# stm8_sensor.net
KiCad netlist of a schematic drawn in Altium Designer
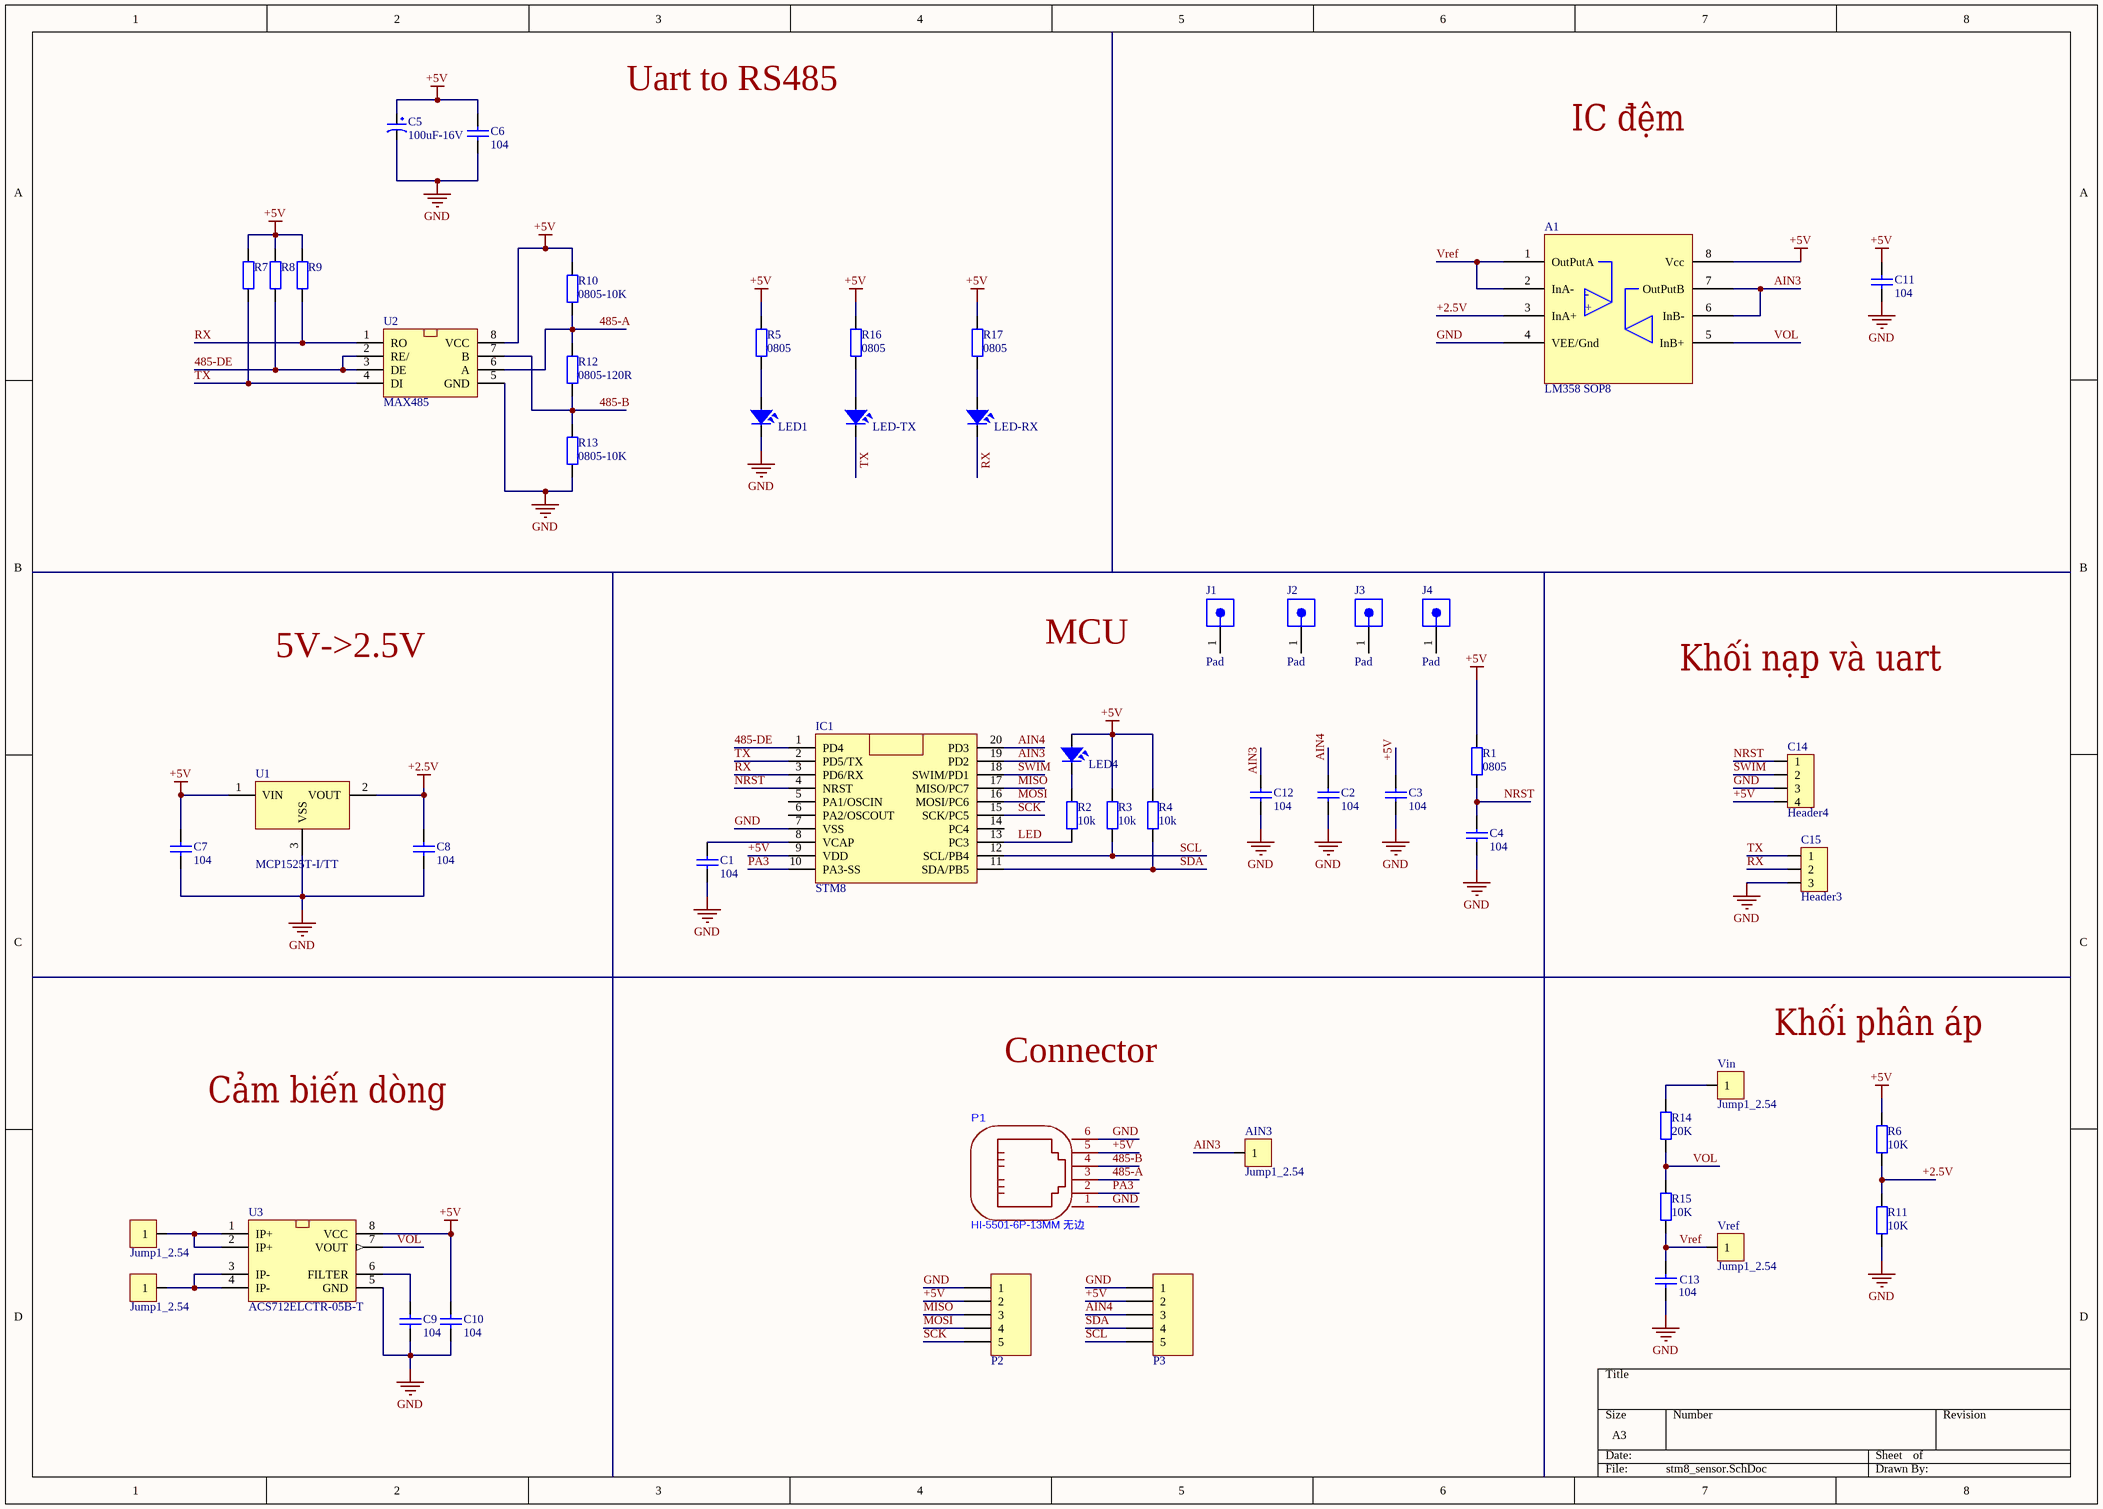
[diagram p0: stm8_sensor.SchDoc]

(export (version "E")
  (design (tool "Eeschema 10.0.6"))
  (components
    (comp (ref "A1")
      (value "LM358 SOP8")
      (footprint "LM358_SOIC")
      (description "Dán")
      (libsource (lib "THU VIEN SCH") (part "LM358"))
    )
    (comp (ref "AIN3")
      (value "Jump1_2.54")
      (footprint "jump1_2.54")
      (libsource (lib "thuviencuazit") (part "jump_1"))
    )
    (comp (ref "C1")
      (value "104")
      (footprint "0805")
      (description "Capacitor (Semiconductor SIM Model)")
      (fields (field (name "PUBLISHER") "Altium Limited"))
      (libsource (lib "Altium_Devzone") (part "Cap 104_SMD"))
    )
    (comp (ref "C2")
      (value "104")
      (footprint "0805")
      (description "Capacitor (Semiconductor SIM Model)")
      (fields (field (name "PUBLISHER") "Altium Limited"))
      (libsource (lib "Altium_Devzone") (part "Cap 104_SMD"))
    )
    (comp (ref "C3")
      (value "104")
      (footprint "0805")
      (description "Capacitor (Semiconductor SIM Model)")
      (fields (field (name "PUBLISHER") "Altium Limited"))
      (libsource (lib "Altium_Devzone") (part "Cap 104_SMD"))
    )
    (comp (ref "C4")
      (value "104")
      (footprint "0805")
      (description "Capacitor (Semiconductor SIM Model)")
      (fields (field (name "PUBLISHER") "Altium Limited"))
      (libsource (lib "Altium_Devzone") (part "Cap 104_SMD"))
    )
    (comp (ref "C5")
      (value "100uF-16V")
      (footprint "tu tantalum smd3216")
      (description "Dán")
      (libsource (lib "THU VIEN SCH") (part "Tu tantalum 1uF 35V SMD3216"))
    )
    (comp (ref "C6")
      (value "104")
      (footprint "tu 0805")
      (description "Dán")
      (libsource (lib "THU VIEN SCH") (part "Tu 0805 104 50V 10%"))
    )
    (comp (ref "C7")
      (value "104")
      (footprint "Tu 0805")
      (description "Dán")
      (libsource (lib "THU VIEN SCH") (part "Tu 104"))
    )
    (comp (ref "C8")
      (value "104")
      (footprint "Tu 0805")
      (description "Dán")
      (libsource (lib "THU VIEN SCH") (part "Tu 104"))
    )
    (comp (ref "C9")
      (value "104")
      (footprint "Tu 0805")
      (description "Dán")
      (libsource (lib "THU VIEN SCH") (part "Tu 104"))
    )
    (comp (ref "C10")
      (value "104")
      (footprint "Tu 0805")
      (description "Dán")
      (libsource (lib "THU VIEN SCH") (part "Tu 104"))
    )
    (comp (ref "C11")
      (value "104")
      (footprint "Tu 0805")
      (description "Dán")
      (libsource (lib "THU VIEN SCH") (part "Tu 104"))
    )
    (comp (ref "C12")
      (value "104")
      (footprint "0805")
      (description "Capacitor (Semiconductor SIM Model)")
      (fields (field (name "PUBLISHER") "Altium Limited"))
      (libsource (lib "Altium_Devzone") (part "Cap 104_SMD"))
    )
    (comp (ref "C13")
      (value "104")
      (footprint "Tu 0805")
      (description "Dán")
      (libsource (lib "THU VIEN SCH") (part "Tu 104"))
    )
    (comp (ref "C14")
      (value "Header4")
      (footprint "Header4")
      (description "Header IDC, 4 x 1 Pin Vertical 2.54mm Pitch (Non-Boxed, Male)")
      (fields
        (field (name "MANUFACTURER") "Würth Elektronik eiSos GmbH")
        (field (name "PARTNO") "613002143121")
        (field (name "CREATED BY") "Karrer Zheng")
      )
      (libsource (lib "Altium_Devzone") (part "Header4"))
    )
    (comp (ref "C15")
      (value "Header3")
      (footprint "Header3")
      (description "Header IDC, 3 x 1 Pin Vertical 2.54mm Pitch (Non-Boxed, Male)")
      (fields
        (field (name "MANUFACTURER") "Würth Elektronik eiSos GmbH")
        (field (name "PARTNO") "613002143121")
        (field (name "CREATED BY") "Karrer Zheng")
      )
      (libsource (lib "Altium_Devzone") (part "Header3"))
    )
    (comp (ref "IC1")
      (value "STM8")
      (footprint "TSSOP 20PIN")
      (description "STM32 ARM MCU")
      (libsource (lib "Altium_Devzone") (part "STM8S103F3_20P"))
    )
    (comp (ref "IP+") (value "Jump1_2.54") (footprint "jump1_2.54") (libsource (lib "") (part "jump_1_1")))
    (comp (ref "IP-") (value "Jump1_2.54") (footprint "jump1_2.54") (libsource (lib "") (part "jump_1_1")))
    (comp (ref "J1")
      (value "Pad")
      (footprint "MinhTien_PCBLib:Pad_4.5x4.5_hole_3.2mm_no_legend")
      (fields (field (name "PUBLISHER") "Altium Limited"))
      (libsource (lib "MinhTien_SCHLib") (part "Pad"))
    )
    (comp (ref "J2")
      (value "Pad")
      (footprint "MinhTien_PCBLib:Pad_4.5x4.5_hole_3.2mm_no_legend")
      (fields (field (name "PUBLISHER") "Altium Limited"))
      (libsource (lib "MinhTien_SCHLib") (part "Pad"))
    )
    (comp (ref "J3")
      (value "Pad")
      (footprint "MinhTien_PCBLib:Pad_4.5x4.5_hole_3.2mm_no_legend")
      (fields (field (name "PUBLISHER") "Altium Limited"))
      (libsource (lib "MinhTien_SCHLib") (part "Pad"))
    )
    (comp (ref "J4")
      (value "Pad")
      (footprint "MinhTien_PCBLib:Pad_4.5x4.5_hole_3.2mm_no_legend")
      (fields (field (name "PUBLISHER") "Altium Limited"))
      (libsource (lib "MinhTien_SCHLib") (part "Pad"))
    )
    (comp (ref "LED-RX")
      (value "LED")
      (footprint "LED-5-Green")
      (description "LED Single colour Green and Red")
      (libsource (lib "Altium_Devzone") (part "LED"))
    )
    (comp (ref "LED-TX")
      (value "LED")
      (footprint "LED-5-BLUE")
      (description "LED Single colour Green and Red")
      (libsource (lib "Altium_Devzone") (part "LED"))
    )
    (comp (ref "LED1")
      (value "LED")
      (footprint "LED-5-Yellow")
      (description "LED Single colour Green and Red")
      (libsource (lib "Altium_Devzone") (part "LED"))
    )
    (comp (ref "LED4")
      (value "LED")
      (footprint "LED-5-RED")
      (description "LED Single colour Green and Red")
      (libsource (lib "Altium_Devzone") (part "LED"))
    )
    (comp (ref "P1")
      (value "HI-5501-6P-13MM 无边")
      (footprint "RJ11-TH_PCB-6P6C-90")
      (libsource (lib "thuviencuazit") (part "HI-5501-6P-13MM 无边"))
    )
    (comp (ref "P2")
      (value "Connector")
      (footprint "MinhTien_PCBLib:JST-XH_B5B-XH-A")
      (libsource (lib "MinhTien_SCHLib") (part "Connector_5pin"))
    )
    (comp (ref "P3")
      (value "Connector")
      (footprint "MinhTien_PCBLib:JST-XH_B5B-XH-A")
      (libsource (lib "MinhTien_SCHLib") (part "Connector_5pin"))
    )
    (comp (ref "R1")
      (value "0805")
      (footprint "DIEN TRO 0805")
      (description "Resistor SMD 0805")
      (fields (field (name "Comment") "R0805") (field (name "PUBLISHER") "Altium Limited"))
      (libsource (lib "Altium_Devzone") (part "R0805"))
    )
    (comp (ref "R2")
      (value "10k")
      (footprint "DIEN TRO 0805")
      (description "Resistor SMD 0805")
      (fields (field (name "Comment") "R0805") (field (name "PUBLISHER") "Altium Limited"))
      (libsource (lib "Altium_Devzone") (part "R0805"))
    )
    (comp (ref "R3")
      (value "10k")
      (footprint "DIEN TRO 0805")
      (description "Resistor SMD 0805")
      (fields (field (name "Comment") "R0805") (field (name "PUBLISHER") "Altium Limited"))
      (libsource (lib "Altium_Devzone") (part "R0805"))
    )
    (comp (ref "R4")
      (value "10k")
      (footprint "DIEN TRO 0805")
      (description "Resistor SMD 0805")
      (fields (field (name "Comment") "R0805") (field (name "PUBLISHER") "Altium Limited"))
      (libsource (lib "Altium_Devzone") (part "R0805"))
    )
    (comp (ref "R5")
      (value "0805")
      (footprint "DIEN TRO 0805")
      (description "Resistor SMD 0805")
      (fields (field (name "Comment") "R0805") (field (name "PUBLISHER") "Altium Limited"))
      (libsource (lib "Altium_Devzone") (part "R0805"))
    )
    (comp (ref "R6")
      (value "10K")
      (footprint "DIEN TRO 0805")
      (description "Resistor SMD 0805")
      (fields (field (name "Comment") "R0805") (field (name "PUBLISHER") "Altium Limited"))
      (libsource (lib "Altium_Devzone") (part "R0805"))
    )
    (comp (ref "R7")
      (value "R0805")
      (footprint "DIEN TRO 0805")
      (description "Resistor SMD 0805")
      (fields (field (name "PUBLISHER") "Altium Limited"))
      (libsource (lib "Altium_Devzone") (part "R0805"))
    )
    (comp (ref "R8")
      (value "R0805")
      (footprint "DIEN TRO 0805")
      (description "Resistor SMD 0805")
      (fields (field (name "PUBLISHER") "Altium Limited"))
      (libsource (lib "Altium_Devzone") (part "R0805"))
    )
    (comp (ref "R9")
      (value "R0805")
      (footprint "DIEN TRO 0805")
      (description "Resistor SMD 0805")
      (fields (field (name "PUBLISHER") "Altium Limited"))
      (libsource (lib "Altium_Devzone") (part "R0805"))
    )
    (comp (ref "R10")
      (value "0805-10K")
      (footprint "DIEN TRO 0805")
      (description "Resistor SMD 0805")
      (fields (field (name "Comment") "R0805") (field (name "PUBLISHER") "Altium Limited"))
      (libsource (lib "Altium_Devzone") (part "R0805"))
    )
    (comp (ref "R11")
      (value "10K")
      (footprint "DIEN TRO 0805")
      (description "Resistor SMD 0805")
      (fields (field (name "Comment") "R0805") (field (name "PUBLISHER") "Altium Limited"))
      (libsource (lib "Altium_Devzone") (part "R0805"))
    )
    (comp (ref "R12")
      (value "0805-120R")
      (footprint "DIEN TRO 0805")
      (description "Resistor SMD 0805")
      (fields (field (name "Comment") "R0805") (field (name "PUBLISHER") "Altium Limited"))
      (libsource (lib "Altium_Devzone") (part "R0805"))
    )
    (comp (ref "R13")
      (value "0805-10K")
      (footprint "DIEN TRO 0805")
      (description "Resistor SMD 0805")
      (fields (field (name "Comment") "R0805") (field (name "PUBLISHER") "Altium Limited"))
      (libsource (lib "Altium_Devzone") (part "R0805"))
    )
    (comp (ref "R14")
      (value "20K")
      (footprint "DIEN TRO 0805")
      (description "Resistor SMD 0805")
      (fields (field (name "Comment") "R0805") (field (name "PUBLISHER") "Altium Limited"))
      (libsource (lib "Altium_Devzone") (part "R0805"))
    )
    (comp (ref "R15")
      (value "10K")
      (footprint "DIEN TRO 0805")
      (description "Resistor SMD 0805")
      (fields (field (name "Comment") "R0805") (field (name "PUBLISHER") "Altium Limited"))
      (libsource (lib "Altium_Devzone") (part "R0805"))
    )
    (comp (ref "R16")
      (value "0805")
      (footprint "DIEN TRO 0805")
      (description "Resistor SMD 0805")
      (fields (field (name "Comment") "R0805") (field (name "PUBLISHER") "Altium Limited"))
      (libsource (lib "Altium_Devzone") (part "R0805"))
    )
    (comp (ref "R17")
      (value "0805")
      (footprint "DIEN TRO 0805")
      (description "Resistor SMD 0805")
      (fields (field (name "Comment") "R0805") (field (name "PUBLISHER") "Altium Limited"))
      (libsource (lib "Altium_Devzone") (part "R0805"))
    )
    (comp (ref "U1")
      (value "MCP1525T-I/TT")
      (footprint "MinhTien_PCBLib:SOT23")
      (description "2.5V And 4.096V Voltage References")
      (libsource (lib "MinhTien_SCHLib") (part "MCP1525T"))
    )
    (comp (ref "U2")
      (value "MAX485")
      (footprint "MinhTien_PcbLib:SOP8_L")
      (libsource (lib "MinhTien_SCHLib") (part "MAX485"))
    )
    (comp (ref "U3")
      (value "ACS712ELCTR-05B-T")
      (footprint "MinhTien_PcbLib:SOP8_L")
      (description "SENSOR CURRENT HALL 5A AC/DC")
      (libsource (lib "MinhTien_SCHLib") (part "ACS712ELCTR-05B-T"))
    )
    (comp (ref "Vin")
      (value "Jump1_2.54")
      (footprint "jump1_2.54")
      (libsource (lib "thuviencuazit") (part "jump_1"))
    )
    (comp (ref "Vref")
      (value "Jump1_2.54")
      (footprint "jump1_2.54")
      (libsource (lib "thuviencuazit") (part "jump_1"))
    )
  )
  (nets
    (net (code "1") (name "+2.5V") (class "Default")
      (node (ref "A1") (pin "3") (pinfunction "InA+_3") (pintype "passive"))
      (node (ref "C8") (pin "2") (pinfunction "2_2") (pintype "passive"))
      (node (ref "R11") (pin "2") (pinfunction "2_2") (pintype "passive"))
      (node (ref "R6") (pin "1") (pinfunction "1_1") (pintype "passive"))
      (node (ref "U1") (pin "2") (pinfunction "VOUT_2") (pintype "passive"))
    )
    (net (code "2") (name "+5V") (class "Default")
      (node (ref "A1") (pin "8") (pinfunction "Vcc_8") (pintype "passive"))
      (node (ref "C10") (pin "2") (pinfunction "2_2") (pintype "passive"))
      (node (ref "C11") (pin "2") (pinfunction "2_2") (pintype "passive"))
      (node (ref "C14") (pin "4") (pinfunction "4_4") (pintype "passive"))
      (node (ref "C3") (pin "2") (pintype "passive"))
      (node (ref "C5") (pin "1") (pinfunction "1_1") (pintype "passive"))
      (node (ref "C6") (pin "1") (pinfunction "1_1") (pintype "passive"))
      (node (ref "C7") (pin "2") (pinfunction "2_2") (pintype "passive"))
      (node (ref "IC1") (pin "9") (pinfunction "VDD_9") (pintype "passive"))
      (node (ref "LED4") (pin "1") (pinfunction "1_1") (pintype "passive"))
      (node (ref "P1") (pin "5") (pinfunction "5_5") (pintype "passive"))
      (node (ref "P2") (pin "2") (pinfunction "2_2") (pintype "passive"))
      (node (ref "P3") (pin "2") (pinfunction "2_2") (pintype "passive"))
      (node (ref "R1") (pin "2") (pinfunction "2_2") (pintype "passive"))
      (node (ref "R10") (pin "2") (pinfunction "2_2") (pintype "passive"))
      (node (ref "R16") (pin "2") (pinfunction "2_2") (pintype "passive"))
      (node (ref "R17") (pin "2") (pinfunction "2_2") (pintype "passive"))
      (node (ref "R3") (pin "2") (pinfunction "2_2") (pintype "passive"))
      (node (ref "R4") (pin "2") (pinfunction "2_2") (pintype "passive"))
      (node (ref "R5") (pin "2") (pinfunction "2_2") (pintype "passive"))
      (node (ref "R6") (pin "2") (pinfunction "2_2") (pintype "passive"))
      (node (ref "R7") (pin "2") (pinfunction "2_2") (pintype "passive"))
      (node (ref "R8") (pin "2") (pinfunction "2_2") (pintype "passive"))
      (node (ref "R9") (pin "2") (pinfunction "2_2") (pintype "passive"))
      (node (ref "U1") (pin "1") (pinfunction "VIN_1") (pintype "passive"))
      (node (ref "U2") (pin "8") (pinfunction "VCC_8") (pintype "power_in"))
      (node (ref "U3") (pin "8") (pinfunction "VCC_8") (pintype "power_in"))
    )
    (net (code "3") (name "/485-A") (class "Default")
      (node (ref "P1") (pin "3") (pinfunction "3_3") (pintype "passive"))
      (node (ref "R10") (pin "1") (pinfunction "1_1") (pintype "passive"))
      (node (ref "R12") (pin "2") (pinfunction "2_2") (pintype "passive"))
      (node (ref "U2") (pin "6") (pinfunction "A_6") (pintype "power_in"))
    )
    (net (code "4") (name "/485-B") (class "Default")
      (node (ref "P1") (pin "4") (pinfunction "4_4") (pintype "passive"))
      (node (ref "R12") (pin "1") (pinfunction "1_1") (pintype "passive"))
      (node (ref "R13") (pin "2") (pinfunction "2_2") (pintype "passive"))
      (node (ref "U2") (pin "7") (pinfunction "B_7") (pintype "power_in"))
    )
    (net (code "5") (name "/485-DE") (class "Default")
      (node (ref "IC1") (pin "1") (pinfunction "PD4_1") (pintype "passive"))
      (node (ref "R8") (pin "1") (pinfunction "1_1") (pintype "passive"))
      (node (ref "U2") (pin "2") (pinfunction "RE/_2") (pintype "power_in"))
      (node (ref "U2") (pin "3") (pinfunction "DE_3") (pintype "power_in"))
    )
    (net (code "6") (name "/AIN3") (class "Default")
      (node (ref "A1") (pin "6") (pinfunction "InB-_6") (pintype "passive"))
      (node (ref "A1") (pin "7") (pinfunction "OutPutB_7") (pintype "passive"))
      (node (ref "AIN3") (pin "1") (pinfunction "1_1") (pintype "passive"))
      (node (ref "C12") (pin "1") (pintype "passive"))
      (node (ref "IC1") (pin "19") (pinfunction "PD2_19") (pintype "passive"))
    )
    (net (code "7") (name "/AIN4") (class "Default")
      (node (ref "C2") (pin "2") (pintype "passive"))
      (node (ref "IC1") (pin "20") (pinfunction "PD3_20") (pintype "passive"))
      (node (ref "P3") (pin "3") (pinfunction "3_3") (pintype "passive"))
    )
    (net (code "8") (name "/LED") (class "Default")
      (node (ref "IC1") (pin "13") (pinfunction "PC3_13") (pintype "passive"))
      (node (ref "R2") (pin "1") (pinfunction "1_1") (pintype "passive"))
    )
    (net (code "9") (name "/MISO") (class "Default")
      (node (ref "IC1") (pin "17") (pinfunction "MISO/PC7_17") (pintype "passive"))
      (node (ref "P2") (pin "3") (pinfunction "3_3") (pintype "passive"))
    )
    (net (code "10") (name "/MOSI") (class "Default")
      (node (ref "IC1") (pin "16") (pinfunction "MOSI/PC6_16") (pintype "passive"))
      (node (ref "P2") (pin "4") (pinfunction "4_4") (pintype "passive"))
    )
    (net (code "11") (name "/NRST") (class "Default")
      (node (ref "C14") (pin "1") (pinfunction "1_1") (pintype "passive"))
      (node (ref "C4") (pin "2") (pintype "passive"))
      (node (ref "IC1") (pin "4") (pinfunction "NRST_4") (pintype "passive"))
      (node (ref "R1") (pin "1") (pinfunction "1_1") (pintype "passive"))
    )
    (net (code "12") (name "/PA3") (class "Default")
      (node (ref "IC1") (pin "10") (pinfunction "PA3-SS_10") (pintype "passive"))
      (node (ref "P1") (pin "2") (pinfunction "2_2") (pintype "passive"))
    )
    (net (code "13") (name "/RX") (class "Default")
      (node (ref "C15") (pin "2") (pinfunction "2_2") (pintype "passive"))
      (node (ref "IC1") (pin "3") (pinfunction "PD6/RX_3") (pintype "passive"))
      (node (ref "LED-RX") (pin "2") (pinfunction "2_2") (pintype "passive"))
      (node (ref "R9") (pin "1") (pinfunction "1_1") (pintype "passive"))
      (node (ref "U2") (pin "1") (pinfunction "RO_1") (pintype "power_in"))
    )
    (net (code "14") (name "/SCK") (class "Default")
      (node (ref "IC1") (pin "15") (pinfunction "SCK/PC5_15") (pintype "passive"))
      (node (ref "P2") (pin "5") (pinfunction "5_5") (pintype "passive"))
    )
    (net (code "15") (name "/SCL") (class "Default")
      (node (ref "IC1") (pin "12") (pinfunction "SCL/PB4_12") (pintype "passive"))
      (node (ref "P3") (pin "5") (pinfunction "5_5") (pintype "passive"))
      (node (ref "R3") (pin "1") (pinfunction "1_1") (pintype "passive"))
    )
    (net (code "16") (name "/SDA") (class "Default")
      (node (ref "IC1") (pin "11") (pinfunction "SDA/PB5_11") (pintype "passive"))
      (node (ref "P3") (pin "4") (pinfunction "4_4") (pintype "passive"))
      (node (ref "R4") (pin "1") (pinfunction "1_1") (pintype "passive"))
    )
    (net (code "17") (name "/SWIM") (class "Default")
      (node (ref "C14") (pin "2") (pinfunction "2_2") (pintype "passive"))
      (node (ref "IC1") (pin "18") (pinfunction "SWIM/PD1_18") (pintype "passive"))
    )
    (net (code "18") (name "/TX") (class "Default")
      (node (ref "C15") (pin "1") (pinfunction "1_1") (pintype "passive"))
      (node (ref "IC1") (pin "2") (pinfunction "PD5/TX_2") (pintype "passive"))
      (node (ref "LED-TX") (pin "2") (pinfunction "2_2") (pintype "passive"))
      (node (ref "R7") (pin "1") (pinfunction "1_1") (pintype "passive"))
      (node (ref "U2") (pin "4") (pinfunction "DI_4") (pintype "power_in"))
    )
    (net (code "19") (name "/VOL") (class "Default")
      (node (ref "A1") (pin "5") (pinfunction "InB+_5") (pintype "passive"))
      (node (ref "R14") (pin "1") (pinfunction "1_1") (pintype "passive"))
      (node (ref "R15") (pin "2") (pinfunction "2_2") (pintype "passive"))
      (node (ref "U3") (pin "7") (pinfunction "VOUT_7") (pintype "output"))
    )
    (net (code "20") (name "/Vref") (class "Default")
      (node (ref "A1") (pin "1") (pinfunction "OutPutA_1") (pintype "passive"))
      (node (ref "A1") (pin "2") (pinfunction "InA-_2") (pintype "passive"))
      (node (ref "C13") (pin "2") (pinfunction "2_2") (pintype "passive"))
      (node (ref "R15") (pin "1") (pinfunction "1_1") (pintype "passive"))
      (node (ref "Vref") (pin "1") (pinfunction "1_1") (pintype "passive"))
    )
    (net (code "21") (name "GND") (class "Default")
      (node (ref "A1") (pin "4") (pinfunction "VEE/Gnd_4") (pintype "passive"))
      (node (ref "C1") (pin "1") (pintype "passive"))
      (node (ref "C10") (pin "1") (pinfunction "1_1") (pintype "passive"))
      (node (ref "C11") (pin "1") (pinfunction "1_1") (pintype "passive"))
      (node (ref "C12") (pin "2") (pintype "passive"))
      (node (ref "C13") (pin "1") (pinfunction "1_1") (pintype "passive"))
      (node (ref "C14") (pin "3") (pinfunction "3_3") (pintype "passive"))
      (node (ref "C15") (pin "3") (pinfunction "3_3") (pintype "passive"))
      (node (ref "C2") (pin "1") (pintype "passive"))
      (node (ref "C3") (pin "1") (pintype "passive"))
      (node (ref "C4") (pin "1") (pintype "passive"))
      (node (ref "C5") (pin "2") (pinfunction "2_2") (pintype "passive"))
      (node (ref "C6") (pin "2") (pinfunction "2_2") (pintype "passive"))
      (node (ref "C7") (pin "1") (pinfunction "1_1") (pintype "passive"))
      (node (ref "C8") (pin "1") (pinfunction "1_1") (pintype "passive"))
      (node (ref "C9") (pin "1") (pinfunction "1_1") (pintype "passive"))
      (node (ref "IC1") (pin "7") (pinfunction "VSS_7") (pintype "passive"))
      (node (ref "LED1") (pin "2") (pinfunction "2_2") (pintype "passive"))
      (node (ref "P1") (pin "1") (pinfunction "1_1") (pintype "passive"))
      (node (ref "P1") (pin "6") (pinfunction "6_6") (pintype "passive"))
      (node (ref "P2") (pin "1") (pinfunction "1_1") (pintype "passive"))
      (node (ref "P3") (pin "1") (pinfunction "1_1") (pintype "passive"))
      (node (ref "R11") (pin "1") (pinfunction "1_1") (pintype "passive"))
      (node (ref "R13") (pin "1") (pinfunction "1_1") (pintype "passive"))
      (node (ref "U1") (pin "3") (pinfunction "VSS_3") (pintype "passive"))
      (node (ref "U2") (pin "5") (pinfunction "GND_5") (pintype "power_in"))
      (node (ref "U3") (pin "5") (pinfunction "GND_5") (pintype "power_in"))
    )
    (net (code "22") (name "Net-(IC1-VCAP)") (class "Default")
      (node (ref "C1") (pin "2") (pintype "passive"))
      (node (ref "IC1") (pin "8") (pinfunction "VCAP_8") (pintype "passive"))
    )
    (net (code "23") (name "Net-(IP+-Pad1)") (class "Default")
      (node (ref "IP+") (pin "1") (pinfunction "1_1") (pintype "passive"))
      (node (ref "U3") (pin "1") (pinfunction "IP+_1") (pintype "passive"))
      (node (ref "U3") (pin "2") (pinfunction "IP+_2") (pintype "passive"))
    )
    (net (code "24") (name "Net-(IP--Pad1)") (class "Default")
      (node (ref "IP-") (pin "1") (pinfunction "1_1") (pintype "passive"))
      (node (ref "U3") (pin "3") (pinfunction "IP-_3") (pintype "passive"))
      (node (ref "U3") (pin "4") (pinfunction "IP-_4") (pintype "passive"))
    )
    (net (code "25") (name "Net-(LED-RX-Pad1)") (class "Default")
      (node (ref "LED-RX") (pin "1") (pinfunction "1_1") (pintype "passive"))
      (node (ref "R17") (pin "1") (pinfunction "1_1") (pintype "passive"))
    )
    (net (code "26") (name "Net-(LED-TX-Pad1)") (class "Default")
      (node (ref "LED-TX") (pin "1") (pinfunction "1_1") (pintype "passive"))
      (node (ref "R16") (pin "1") (pinfunction "1_1") (pintype "passive"))
    )
    (net (code "27") (name "Net-(LED1-Pad1)") (class "Default")
      (node (ref "LED1") (pin "1") (pinfunction "1_1") (pintype "passive"))
      (node (ref "R5") (pin "1") (pinfunction "1_1") (pintype "passive"))
    )
    (net (code "28") (name "Net-(LED4-Pad2)") (class "Default")
      (node (ref "LED4") (pin "2") (pinfunction "2_2") (pintype "passive"))
      (node (ref "R2") (pin "2") (pinfunction "2_2") (pintype "passive"))
    )
    (net (code "29") (name "Net-(R14-Pad2)") (class "Default")
      (node (ref "R14") (pin "2") (pinfunction "2_2") (pintype "passive"))
      (node (ref "Vin") (pin "1") (pinfunction "1_1") (pintype "passive"))
    )
    (net (code "30") (name "Net-(U3-FILTER)") (class "Default")
      (node (ref "C9") (pin "2") (pinfunction "2_2") (pintype "passive"))
      (node (ref "U3") (pin "6") (pinfunction "FILTER_6") (pintype "passive"))
    )
    (net (code "31") (name "unconnected-(IC1-PA1{slash}OSCIN-Pad5)") (class "Default")
      (node (ref "IC1") (pin "5") (pinfunction "PA1/OSCIN_5") (pintype "passive"))
    )
    (net (code "32") (name "unconnected-(IC1-PA2{slash}OSCOUT-Pad6)") (class "Default")
      (node (ref "IC1") (pin "6") (pinfunction "PA2/OSCOUT_6") (pintype "passive"))
    )
    (net (code "33") (name "unconnected-(IC1-PC4-Pad14)") (class "Default")
      (node (ref "IC1") (pin "14") (pinfunction "PC4_14") (pintype "passive"))
    )
    (net (code "34") (name "unconnected-(J1-Pad1)") (class "Default")
      (node (ref "J1") (pin "1") (pinfunction "1_1") (pintype "passive"))
    )
    (net (code "35") (name "unconnected-(J2-Pad1)") (class "Default")
      (node (ref "J2") (pin "1") (pinfunction "1_1") (pintype "passive"))
    )
    (net (code "36") (name "unconnected-(J3-Pad1)") (class "Default")
      (node (ref "J3") (pin "1") (pinfunction "1_1") (pintype "passive"))
    )
    (net (code "37") (name "unconnected-(J4-Pad1)") (class "Default")
      (node (ref "J4") (pin "1") (pinfunction "1_1") (pintype "passive"))
    )
  )
)
